# Power_Supply.net
KiCad netlist of a schematic drawn in Altium Designer
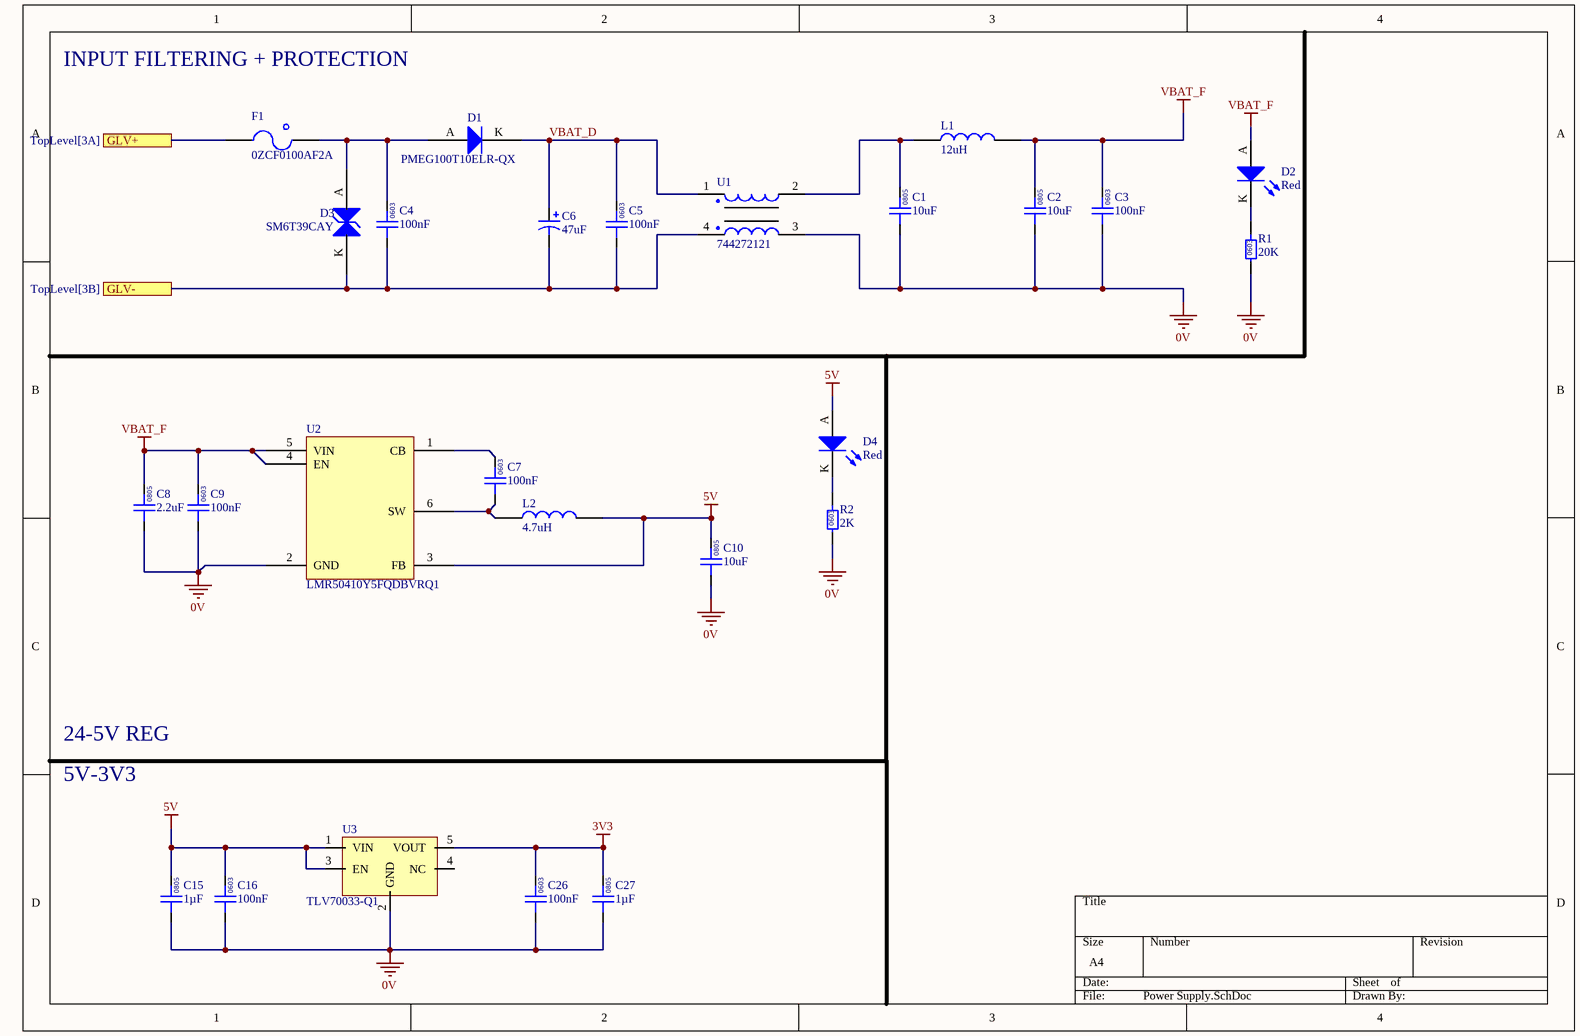
[diagram p0: Power Supply.SchDoc]

(export (version "E")
  (design (tool "Eeschema 10.0.6"))
  (components
    (comp (ref "C1")
      (value "10uF")
      (footprint "0805")
      (fields
        (field (name "PART NUMBER") "GRM21BR6YA106KE43L")
        (field (name "MANUFACTURER") "muRata")
        (field (name "TOLERANCE") "10%")
      )
      (libsource (lib "ts_standard_library") (part "Capacitor 0805"))
    )
    (comp (ref "C2")
      (value "10uF")
      (footprint "0805")
      (fields
        (field (name "PART NUMBER") "GRM21BR6YA106KE43L")
        (field (name "MANUFACTURER") "muRata")
        (field (name "TOLERANCE") "10%")
      )
      (libsource (lib "ts_standard_library") (part "Capacitor 0805"))
    )
    (comp (ref "C3")
      (value "100nF")
      (footprint "0603")
      (fields
        (field (name "PART NUMBER") "GCM188L81H104KA57D")
        (field (name "MANUFACTURER") "muRata")
        (field (name "TOLERANCE") "±10%")
      )
      (libsource (lib "ts_standard_library") (part "Capacitor 0603"))
    )
    (comp (ref "C4")
      (value "100nF")
      (footprint "0603")
      (fields
        (field (name "PART NUMBER") "GCM188L81H104KA57D")
        (field (name "MANUFACTURER") "muRata")
        (field (name "TOLERANCE") "±10%")
      )
      (libsource (lib "ts_standard_library") (part "Capacitor 0603"))
    )
    (comp (ref "C5")
      (value "100nF")
      (footprint "0603")
      (fields
        (field (name "PART NUMBER") "GCM188L81H104KA57D")
        (field (name "MANUFACTURER") "muRata")
        (field (name "TOLERANCE") "±10%")
      )
      (libsource (lib "ts_standard_library") (part "Capacitor 0603"))
    )
    (comp (ref "C6")
      (value "47uF")
      (footprint "CHEMI-CON ELCO")
      (fields (field (name "PART NUMBER") "HHXA350ARA470MF61G"))
      (libsource (lib "ts_standard_library") (part "Capacitor (Polarised)"))
    )
    (comp (ref "C7")
      (value "100nF")
      (footprint "0603")
      (fields
        (field (name "PART NUMBER") "GCM188L81H104KA57D")
        (field (name "MANUFACTURER") "muRata")
        (field (name "TOLERANCE") "±10%")
      )
      (libsource (lib "ts_standard_library") (part "Capacitor 0603"))
    )
    (comp (ref "C8")
      (value "2.2uF")
      (footprint "0805")
      (fields
        (field (name "PART NUMBER") "GRM21BR71E225KE11L")
        (field (name "MANUFACTURER") "Murata Electronics")
        (field (name "TOLERANCE") "±10%")
      )
      (libsource (lib "ts_standard_library") (part "Capacitor 0805"))
    )
    (comp (ref "C9")
      (value "100nF")
      (footprint "0603")
      (fields
        (field (name "PART NUMBER") "GCM188L81H104KA57D")
        (field (name "MANUFACTURER") "muRata")
        (field (name "TOLERANCE") "±10%")
      )
      (libsource (lib "ts_standard_library") (part "Capacitor 0603"))
    )
    (comp (ref "C10")
      (value "10uF")
      (footprint "0805")
      (fields
        (field (name "PART NUMBER") "GRM21BR6YA106KE43L")
        (field (name "MANUFACTURER") "muRata")
        (field (name "TOLERANCE") "10%")
      )
      (libsource (lib "ts_standard_library") (part "Capacitor 0805"))
    )
    (comp (ref "C15")
      (value "1µF")
      (footprint "0805")
      (fields
        (field (name "PART NUMBER") "GCM21BR71H105KA03L")
        (field (name "MANUFACTURER") "muRata")
        (field (name "TOLERANCE") "±10%")
      )
      (libsource (lib "ts_standard_library") (part "Capacitor 0805"))
    )
    (comp (ref "C16")
      (value "100nF")
      (footprint "0603")
      (fields
        (field (name "PART NUMBER") "GCM188L81H104KA57D")
        (field (name "MANUFACTURER") "muRata")
        (field (name "TOLERANCE") "±10%")
      )
      (libsource (lib "ts_standard_library") (part "Capacitor 0603"))
    )
    (comp (ref "C26")
      (value "100nF")
      (footprint "0603")
      (fields
        (field (name "PART NUMBER") "GCM188L81H104KA57D")
        (field (name "MANUFACTURER") "muRata")
        (field (name "TOLERANCE") "±10%")
      )
      (libsource (lib "ts_standard_library") (part "Capacitor 0603"))
    )
    (comp (ref "C27")
      (value "1µF")
      (footprint "0805")
      (fields
        (field (name "PART NUMBER") "GCM21BR71H105KA03L")
        (field (name "MANUFACTURER") "muRata")
        (field (name "TOLERANCE") "±10%")
      )
      (libsource (lib "ts_standard_library") (part "Capacitor 0805"))
    )
    (comp (ref "D1")
      (value "PMEG100T10ELR-QX")
      (footprint "SODFL350X110-2N")
      (description "Diode 100 V 1A Surface Mount SOD-123W")
      (libsource (lib "Team Swinburne") (part "PMEG100T10ELR-QX"))
    )
    (comp (ref "D2")
      (value "Red")
      (footprint "0805 LED")
      (description "Red LED Indication - Discrete 1.75V 0805 (2012 Metric)")
      (fields (field (name "PART NUMBER") "SML-210LTT86") (field (name "MANUFACTURER") "ROHM Semiconductor"))
      (libsource (lib "ts_standard_library") (part "LED"))
    )
    (comp (ref "D3")
      (value "SM6T39CAY")
      (footprint "SM6T39CAY-Footprint-1")
      (description "TVS Diode Single Bi-Dir 33.3V 600W Automotive 2-Pin SMB T/R / TVS DIODE 33.3VWM 69.7VC SMB")
      (libsource (lib "Team Swinburne") (part "SM6T39CAY-Symbol"))
    )
    (comp (ref "D4")
      (value "Red")
      (footprint "0805 LED")
      (description "Red LED Indication - Discrete 1.75V 0805 (2012 Metric)")
      (fields (field (name "PART NUMBER") "SML-210LTT86") (field (name "MANUFACTURER") "ROHM Semiconductor"))
      (libsource (lib "ts_standard_library") (part "LED"))
    )
    (comp (ref "F1")
      (value "0ZCF0100AF2A")
      (footprint "2920")
      (description "PTC RESET FUSE 60V 1A 292")
      (fields
        (field (name "MANUFACTURER") "Littelfuse Inc.")
        (field (name "DIGIKEY PART NUMBER") "507-2070-1-ND")
      )
      (libsource (lib "ts_standard_library") (part "PTC Fuse"))
    )
    (comp (ref "L1")
      (value "12uH")
      (footprint "1812")
      (fields
        (field (name "PART NUMBER") "RLS-126")
        (field (name "MANUFACTURER") "Recom")
        (field (name "TOLERANCE") "0.2")
      )
      (libsource (lib "ts_standard_library") (part "Inductor"))
    )
    (comp (ref "L2")
      (value "4.7uH")
      (footprint "SRN3015TA-4R7M")
      (fields
        (field (name "PART NUMBER") "SRN4018-4R7M")
        (field (name "MANUFACTURER") "Bourns")
        (field (name "TOLERANCE") "0.2")
      )
      (libsource (lib "ts_standard_library") (part "Inductor"))
    )
    (comp (ref "R1")
      (value "20K")
      (footprint "0603")
      (fields
        (field (name "PART NUMBER") "RC0603FR-0720KL")
        (field (name "MANUFACTURER") "YAGEO")
        (field (name "TOLERANCE") "0.01")
      )
      (libsource (lib "ts_standard_library") (part "Resistor 0603"))
    )
    (comp (ref "R2")
      (value "2K")
      (footprint "0603")
      (fields
        (field (name "PART NUMBER") "RC0603FR-072KL")
        (field (name "MANUFACTURER") "YAGEO")
        (field (name "TOLERANCE") "0.01")
      )
      (libsource (lib "ts_standard_library") (part "Resistor 0603"))
    )
    (comp (ref "U1")
      (value "744272121")
      (footprint "Wurth 4-PC Pad")
      (fields
        (field (name "MANUFACTURER") "Wurth Electronics Inc")
        (field (name "DIGIKEY PART NUMBER") "732-1489-1-ND")
      )
      (libsource (lib "ts_standard_library") (part "CM Choke"))
    )
    (comp (ref "U2")
      (value "LMR50410Y5FQDBVRQ1")
      (footprint "TI-SOT23-6")
      (description "IC REG BUCK 5V 1A SOT23-6")
      (fields (field (name "PART NUMBER") "LMR50410-Q1") (field (name "MANUFACTURER") "Texas Instruments"))
      (libsource (lib "ts_standard_library") (part "LMR50410Y5FQDBVRQ1"))
    )
    (comp (ref "U3")
      (value "TLV70033-Q1")
      (footprint "TI SOT-23-5")
      (description "IC REG LINEAR 3.3V 200MA SOT23-5")
      (fields
        (field (name "MANUFACTURER") "Texas Instruments")
        (field (name "DIGIKEY PART NUMBER") "296-27780-1-ND")
      )
      (libsource (lib "ts_standard_library") (part "TLV70033-Q1"))
    )
  )
  (nets
    (net (code "1") (name "/GLV+") (class "Default")
      (node (ref "F1") (pin "1") (pinfunction "1_1") (pintype "passive"))
    )
    (net (code "2") (name "/GLV-") (class "Default")
      (node (ref "C4") (pin "1") (pinfunction "1_1") (pintype "passive"))
      (node (ref "C5") (pin "1") (pinfunction "1_1") (pintype "passive"))
      (node (ref "C6") (pin "1") (pinfunction "1_1") (pintype "passive"))
      (node (ref "D3") (pin "K") (pintype "passive"))
      (node (ref "U1") (pin "4") (pinfunction "4_4") (pintype "passive"))
    )
    (net (code "3") (name "/VBAT_D") (class "Default")
      (node (ref "C5") (pin "2") (pinfunction "2_2") (pintype "passive"))
      (node (ref "C6") (pin "2") (pinfunction "2_2") (pintype "passive"))
      (node (ref "D1") (pin "K") (pintype "passive"))
      (node (ref "U1") (pin "1") (pinfunction "1_1") (pintype "passive"))
    )
    (net (code "4") (name "0V") (class "Default")
      (node (ref "C1") (pin "1") (pinfunction "1_1") (pintype "passive"))
      (node (ref "C10") (pin "1") (pinfunction "1_1") (pintype "passive"))
      (node (ref "C15") (pin "1") (pinfunction "1_1") (pintype "passive"))
      (node (ref "C16") (pin "1") (pinfunction "1_1") (pintype "passive"))
      (node (ref "C2") (pin "1") (pinfunction "1_1") (pintype "passive"))
      (node (ref "C26") (pin "1") (pinfunction "1_1") (pintype "passive"))
      (node (ref "C27") (pin "1") (pinfunction "1_1") (pintype "passive"))
      (node (ref "C3") (pin "1") (pinfunction "1_1") (pintype "passive"))
      (node (ref "C8") (pin "1") (pinfunction "1_1") (pintype "passive"))
      (node (ref "C9") (pin "1") (pinfunction "1_1") (pintype "passive"))
      (node (ref "R1") (pin "1") (pinfunction "1_1") (pintype "passive"))
      (node (ref "R2") (pin "1") (pinfunction "1_1") (pintype "passive"))
      (node (ref "U1") (pin "3") (pinfunction "3_3") (pintype "power_in"))
      (node (ref "U2") (pin "2") (pinfunction "GND_2") (pintype "passive"))
      (node (ref "U3") (pin "2") (pinfunction "GND_2") (pintype "passive"))
    )
    (net (code "5") (name "3V3") (class "Default")
      (node (ref "C26") (pin "2") (pinfunction "2_2") (pintype "passive"))
      (node (ref "C27") (pin "2") (pinfunction "2_2") (pintype "passive"))
      (node (ref "U3") (pin "5") (pinfunction "VOUT_5") (pintype "passive"))
    )
    (net (code "6") (name "5V") (class "Default")
      (node (ref "C10") (pin "2") (pinfunction "2_2") (pintype "passive"))
      (node (ref "C15") (pin "2") (pinfunction "2_2") (pintype "passive"))
      (node (ref "C16") (pin "2") (pinfunction "2_2") (pintype "passive"))
      (node (ref "D4") (pin "A") (pinfunction "A_A") (pintype "passive"))
      (node (ref "L2") (pin "1") (pinfunction "1_1") (pintype "passive"))
      (node (ref "U2") (pin "3") (pinfunction "FB_3") (pintype "passive"))
      (node (ref "U3") (pin "1") (pinfunction "VIN_1") (pintype "passive"))
      (node (ref "U3") (pin "3") (pinfunction "EN_3") (pintype "passive"))
    )
    (net (code "7") (name "Net-(C1-Pad2)") (class "Default")
      (node (ref "C1") (pin "2") (pinfunction "2_2") (pintype "passive"))
      (node (ref "L1") (pin "2") (pinfunction "2_2") (pintype "passive"))
      (node (ref "U1") (pin "2") (pinfunction "2_2") (pintype "passive"))
    )
    (net (code "8") (name "Net-(C4-Pad2)") (class "Default")
      (node (ref "C4") (pin "2") (pinfunction "2_2") (pintype "passive"))
      (node (ref "D1") (pin "A") (pintype "passive"))
      (node (ref "D3") (pin "A") (pintype "passive"))
      (node (ref "F1") (pin "2") (pinfunction "2_2") (pintype "passive"))
    )
    (net (code "9") (name "Net-(D2-PadK)") (class "Default")
      (node (ref "D2") (pin "K") (pinfunction "K_K") (pintype "passive"))
      (node (ref "R1") (pin "2") (pinfunction "2_2") (pintype "passive"))
    )
    (net (code "10") (name "Net-(D4-PadK)") (class "Default")
      (node (ref "D4") (pin "K") (pinfunction "K_K") (pintype "passive"))
      (node (ref "R2") (pin "2") (pinfunction "2_2") (pintype "passive"))
    )
    (net (code "11") (name "Net-(U2-CB)") (class "Default")
      (node (ref "C7") (pin "2") (pinfunction "2_2") (pintype "passive"))
      (node (ref "U2") (pin "1") (pinfunction "CB_1") (pintype "passive"))
    )
    (net (code "12") (name "Net-(U2-SW)") (class "Default")
      (node (ref "C7") (pin "1") (pinfunction "1_1") (pintype "passive"))
      (node (ref "L2") (pin "2") (pinfunction "2_2") (pintype "passive"))
      (node (ref "U2") (pin "6") (pinfunction "SW_6") (pintype "passive"))
    )
    (net (code "13") (name "VBAT_F") (class "Default")
      (node (ref "C2") (pin "2") (pinfunction "2_2") (pintype "passive"))
      (node (ref "C3") (pin "2") (pinfunction "2_2") (pintype "passive"))
      (node (ref "C8") (pin "2") (pinfunction "2_2") (pintype "passive"))
      (node (ref "C9") (pin "2") (pinfunction "2_2") (pintype "passive"))
      (node (ref "D2") (pin "A") (pinfunction "A_A") (pintype "passive"))
      (node (ref "L1") (pin "1") (pinfunction "1_1") (pintype "passive"))
      (node (ref "U2") (pin "4") (pinfunction "EN_4") (pintype "passive"))
      (node (ref "U2") (pin "5") (pinfunction "VIN_5") (pintype "passive"))
    )
    (net (code "14") (name "unconnected-(U3-NC-Pad4)") (class "Default")
      (node (ref "U3") (pin "4") (pinfunction "NC_4") (pintype "passive"))
    )
  )
)
